# Part12_USB_HUB.net
KiCad netlist of a schematic drawn in Altium Designer
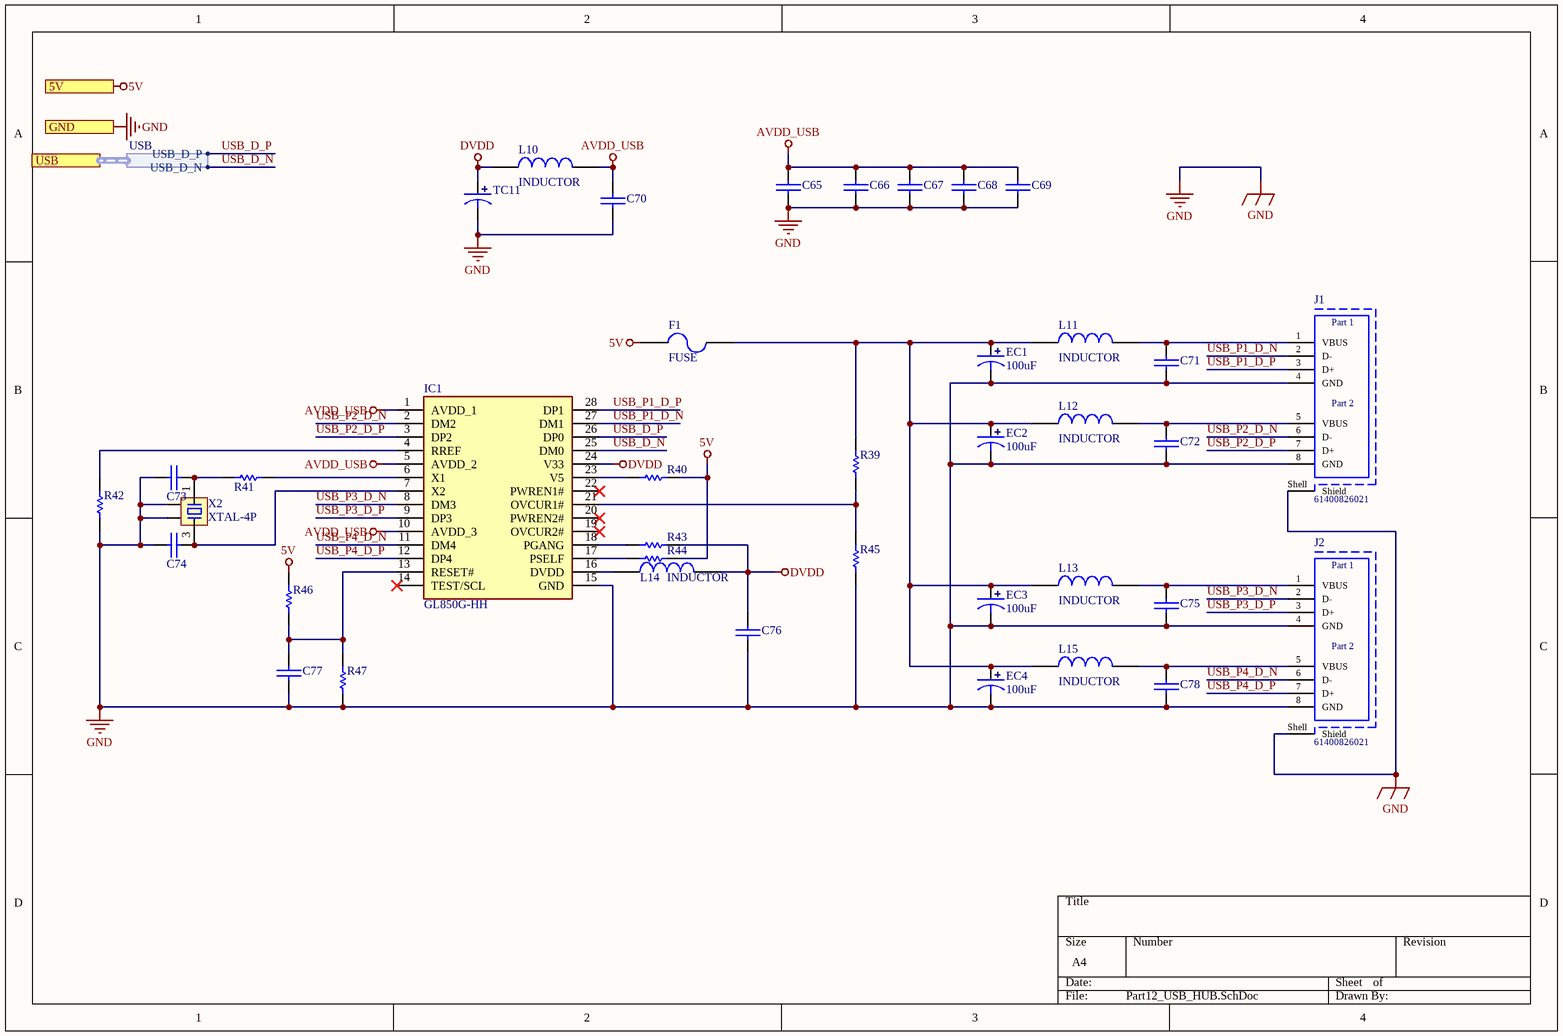
[diagram p0: Part12_USB_HUB.SchDoc]

(export (version "E")
  (design (tool "Eeschema 10.0.6"))
  (components
    (comp (ref "C65")
      (value "100nF/16V")
      (footprint "0402C")
      (description "无极性电容")
      (libsource (lib "电容") (part "CAP"))
    )
    (comp (ref "C66")
      (value "100nF/16V")
      (footprint "0402C")
      (description "无极性电容")
      (libsource (lib "电容") (part "CAP"))
    )
    (comp (ref "C67")
      (value "1uF/16V")
      (footprint "0402C")
      (description "无极性电容")
      (libsource (lib "电容") (part "CAP"))
    )
    (comp (ref "C68")
      (value "1uF/16V")
      (footprint "0402C")
      (description "无极性电容")
      (libsource (lib "电容") (part "CAP"))
    )
    (comp (ref "C69")
      (value "100nF/16V")
      (footprint "0402C")
      (description "无极性电容")
      (libsource (lib "电容") (part "CAP"))
    )
    (comp (ref "C70")
      (value "100nF/16V")
      (footprint "0402C")
      (description "无极性电容")
      (libsource (lib "电容") (part "CAP"))
    )
    (comp (ref "C71")
      (value "100nF/16V")
      (footprint "0603C")
      (description "无极性电容")
      (libsource (lib "电容") (part "CAP"))
    )
    (comp (ref "C72")
      (value "100nF/16V")
      (footprint "0603C")
      (description "无极性电容")
      (libsource (lib "电容") (part "CAP"))
    )
    (comp (ref "C73")
      (value "20pF")
      (footprint "0402C")
      (description "无极性电容")
      (libsource (lib "电容") (part "CAP"))
    )
    (comp (ref "C74")
      (value "20pF")
      (footprint "0402C")
      (description "无极性电容")
      (libsource (lib "电容") (part "CAP"))
    )
    (comp (ref "C75")
      (value "100nF/16V")
      (footprint "0603C")
      (description "无极性电容")
      (libsource (lib "电容") (part "CAP"))
    )
    (comp (ref "C76")
      (value "100nF/16V")
      (footprint "0402C")
      (description "无极性电容")
      (libsource (lib "电容") (part "CAP"))
    )
    (comp (ref "C77")
      (value "1uF/16V")
      (footprint "0402C")
      (description "无极性电容")
      (libsource (lib "电容") (part "CAP"))
    )
    (comp (ref "C78")
      (value "100nF/16V")
      (footprint "0603C")
      (description "无极性电容")
      (libsource (lib "电容") (part "CAP"))
    )
    (comp (ref "EC1")
      (value "100uF")
      (footprint "SMD-EC4.0X4.3X5.4")
      (description "贴片电解电容")
      (libsource (lib "电容") (part "SMD_ECAP"))
    )
    (comp (ref "EC2")
      (value "100uF")
      (footprint "SMD-EC4.0X4.3X5.4")
      (description "贴片电解电容")
      (libsource (lib "电容") (part "SMD_ECAP"))
    )
    (comp (ref "EC3")
      (value "100uF")
      (footprint "SMD-EC4.0X4.3X5.4")
      (description "贴片电解电容")
      (libsource (lib "电容") (part "SMD_ECAP"))
    )
    (comp (ref "EC4")
      (value "100uF")
      (footprint "SMD-EC4.0X4.3X5.4")
      (description "贴片电解电容")
      (libsource (lib "电容") (part "SMD_ECAP"))
    )
    (comp (ref "F1") (value "FUSE") (footprint "FUSE-1210") (libsource (lib "保险丝") (part "FUSE")))
    (comp (ref "IC1")
      (value "GL850G-HH")
      (footprint "SOP65P780X200-28N")
      (description "Integrated Circuit")
      (libsource (lib "SamacSys") (part "GL850G-HH"))
    )
    (comp (ref "J1")
      (value "61400826021")
      (footprint "61400826021")
      (description "USB 2.0 Type A Receptacle WR-COM, Stacked Horizontal, THT")
      (fields (field (name "MANUFACTURER") "Wurth Elektronik") (field (name "PUBLISHER") "WurthElektronik"))
      (libsource (lib "Altium Content Vault") (part "WE-USB-8-1SHLD"))
    )
    (comp (ref "J2")
      (value "61400826021")
      (footprint "61400826021")
      (description "USB 2.0 Type A Receptacle WR-COM, Stacked Horizontal, THT")
      (fields (field (name "MANUFACTURER") "Wurth Elektronik") (field (name "PUBLISHER") "WurthElektronik"))
      (libsource (lib "Altium Content Vault") (part "WE-USB-8-1SHLD"))
    )
    (comp (ref "L10") (value "INDUCTOR") (footprint "0603L") (libsource (lib "电感") (part "INDUCTOR")))
    (comp (ref "L11") (value "INDUCTOR") (footprint "0603L") (libsource (lib "电感") (part "INDUCTOR")))
    (comp (ref "L12") (value "INDUCTOR") (footprint "0603L") (libsource (lib "电感") (part "INDUCTOR")))
    (comp (ref "L13") (value "INDUCTOR") (footprint "0603L") (libsource (lib "电感") (part "INDUCTOR")))
    (comp (ref "L14") (value "INDUCTOR") (footprint "0603L") (libsource (lib "电感") (part "INDUCTOR")))
    (comp (ref "L15") (value "INDUCTOR") (footprint "0603L") (libsource (lib "电感") (part "INDUCTOR")))
    (comp (ref "R39") (value "30K") (footprint "0402R") (libsource (lib "电阻") (part "RES")))
    (comp (ref "R40") (value "0R") (footprint "0402R") (libsource (lib "电阻") (part "RES")))
    (comp (ref "R41") (value "0R") (footprint "0402R") (libsource (lib "电阻") (part "RES")))
    (comp (ref "R42") (value "680R / 1%") (footprint "0402R") (libsource (lib "电阻") (part "RES")))
    (comp (ref "R43") (value "100K") (footprint "0402R") (libsource (lib "电阻") (part "RES")))
    (comp (ref "R44") (value "10K") (footprint "0402R") (libsource (lib "电阻") (part "RES")))
    (comp (ref "R45") (value "30K") (footprint "0402R") (libsource (lib "电阻") (part "RES")))
    (comp (ref "R46") (value "10K") (footprint "0402R") (libsource (lib "电阻") (part "RES")))
    (comp (ref "R47") (value "47K") (footprint "0402R") (libsource (lib "电阻") (part "RES")))
    (comp (ref "TC11")
      (value "4.7uF/6.3V")
      (footprint "TAJ-A/3216")
      (description "钽电容")
      (libsource (lib "电容") (part "TCAP"))
    )
    (comp (ref "X2")
      (value "XTAL-4P")
      (footprint "OSC 3225-4P")
      (description "4脚无源晶振")
      (libsource (lib "晶振") (part "XTAL-4P"))
    )
  )
  (nets
    (net (code "2") (name "/USB_D_N") (class "Default")
      (node (ref "IC1") (pin "25") (pinfunction "DM0_25") (pintype "passive"))
    )
    (net (code "3") (name "/USB_D_P") (class "Default")
      (node (ref "IC1") (pin "26") (pinfunction "DP0_26") (pintype "passive"))
    )
    (net (code "4") (name "/USB_P1_D_N") (class "Default")
      (node (ref "IC1") (pin "27") (pinfunction "DM1_27") (pintype "passive"))
      (node (ref "J1") (pin "2") (pinfunction "D-_2") (pintype "passive"))
    )
    (net (code "5") (name "/USB_P1_D_P") (class "Default")
      (node (ref "IC1") (pin "28") (pinfunction "DP1_28") (pintype "passive"))
      (node (ref "J1") (pin "3") (pinfunction "D+_3") (pintype "passive"))
    )
    (net (code "6") (name "/USB_P2_D_N") (class "Default")
      (node (ref "IC1") (pin "2") (pinfunction "DM2_2") (pintype "passive"))
      (node (ref "J1") (pin "6") (pinfunction "D-_6") (pintype "passive"))
    )
    (net (code "7") (name "/USB_P2_D_P") (class "Default")
      (node (ref "IC1") (pin "3") (pinfunction "DP2_3") (pintype "passive"))
      (node (ref "J1") (pin "7") (pinfunction "D+_7") (pintype "passive"))
    )
    (net (code "8") (name "/USB_P3_D_N") (class "Default")
      (node (ref "IC1") (pin "8") (pinfunction "DM3_8") (pintype "passive"))
      (node (ref "J2") (pin "2") (pinfunction "D-_2") (pintype "passive"))
    )
    (net (code "9") (name "/USB_P3_D_P") (class "Default")
      (node (ref "IC1") (pin "9") (pinfunction "DP3_9") (pintype "passive"))
      (node (ref "J2") (pin "3") (pinfunction "D+_3") (pintype "passive"))
    )
    (net (code "10") (name "/USB_P4_D_N") (class "Default")
      (node (ref "IC1") (pin "11") (pinfunction "DM4_11") (pintype "passive"))
      (node (ref "J2") (pin "6") (pinfunction "D-_6") (pintype "passive"))
    )
    (net (code "11") (name "/USB_P4_D_P") (class "Default")
      (node (ref "IC1") (pin "12") (pinfunction "DP4_12") (pintype "passive"))
      (node (ref "J2") (pin "7") (pinfunction "D+_7") (pintype "passive"))
    )
    (net (code "13") (name "5V") (class "Default")
      (node (ref "F1") (pin "1") (pinfunction "1_1") (pintype "passive"))
      (node (ref "R40") (pin "2") (pinfunction "2_2") (pintype "passive"))
      (node (ref "R44") (pin "2") (pinfunction "2_2") (pintype "passive"))
      (node (ref "R46") (pin "1") (pinfunction "1_1") (pintype "passive"))
    )
    (net (code "14") (name "AVDD_USB") (class "Default")
      (node (ref "C65") (pin "1") (pinfunction "1_1") (pintype "passive"))
      (node (ref "C66") (pin "1") (pinfunction "1_1") (pintype "passive"))
      (node (ref "C67") (pin "1") (pinfunction "1_1") (pintype "passive"))
      (node (ref "C68") (pin "1") (pinfunction "1_1") (pintype "passive"))
      (node (ref "C69") (pin "1") (pinfunction "1_1") (pintype "passive"))
      (node (ref "C70") (pin "1") (pinfunction "1_1") (pintype "passive"))
      (node (ref "IC1") (pin "1") (pinfunction "AVDD_1_1") (pintype "passive"))
      (node (ref "IC1") (pin "10") (pinfunction "AVDD_3_10") (pintype "passive"))
      (node (ref "IC1") (pin "5") (pinfunction "AVDD_2_5") (pintype "passive"))
      (node (ref "L10") (pin "2") (pinfunction "2_2") (pintype "passive"))
    )
    (net (code "15") (name "DVDD") (class "Default")
      (node (ref "C76") (pin "1") (pinfunction "1_1") (pintype "passive"))
      (node (ref "IC1") (pin "24") (pinfunction "V33_24") (pintype "passive"))
      (node (ref "L10") (pin "1") (pinfunction "1_1") (pintype "passive"))
      (node (ref "L14") (pin "2") (pinfunction "2_2") (pintype "passive"))
      (node (ref "R43") (pin "2") (pinfunction "2_2") (pintype "passive"))
      (node (ref "TC11") (pin "1") (pinfunction "1_1") (pintype "passive"))
    )
    (net (code "16") (name "GND") (class "Default")
      (node (ref "C65") (pin "2") (pinfunction "2_2") (pintype "passive"))
      (node (ref "C66") (pin "2") (pinfunction "2_2") (pintype "passive"))
      (node (ref "C67") (pin "2") (pinfunction "2_2") (pintype "passive"))
      (node (ref "C68") (pin "2") (pinfunction "2_2") (pintype "passive"))
      (node (ref "C69") (pin "2") (pinfunction "2_2") (pintype "passive"))
      (node (ref "C70") (pin "2") (pinfunction "2_2") (pintype "passive"))
      (node (ref "C71") (pin "2") (pinfunction "2_2") (pintype "passive"))
      (node (ref "C72") (pin "2") (pinfunction "2_2") (pintype "passive"))
      (node (ref "C73") (pin "1") (pinfunction "1_1") (pintype "passive"))
      (node (ref "C74") (pin "1") (pinfunction "1_1") (pintype "passive"))
      (node (ref "C75") (pin "2") (pinfunction "2_2") (pintype "passive"))
      (node (ref "C76") (pin "2") (pinfunction "2_2") (pintype "passive"))
      (node (ref "C77") (pin "2") (pinfunction "2_2") (pintype "passive"))
      (node (ref "C78") (pin "2") (pinfunction "2_2") (pintype "passive"))
      (node (ref "EC1") (pin "2") (pinfunction "2_2") (pintype "passive"))
      (node (ref "EC2") (pin "2") (pinfunction "2_2") (pintype "passive"))
      (node (ref "EC3") (pin "2") (pinfunction "2_2") (pintype "passive"))
      (node (ref "EC4") (pin "2") (pinfunction "2_2") (pintype "passive"))
      (node (ref "IC1") (pin "15") (pinfunction "GND_15") (pintype "passive"))
      (node (ref "J1") (pin "4") (pinfunction "GND_4") (pintype "passive"))
      (node (ref "J1") (pin "8") (pinfunction "GND_8") (pintype "passive"))
      (node (ref "J1") (pin "Shell") (pinfunction "Shield_Shell") (pintype "passive"))
      (node (ref "J2") (pin "4") (pinfunction "GND_4") (pintype "passive"))
      (node (ref "J2") (pin "8") (pinfunction "GND_8") (pintype "passive"))
      (node (ref "J2") (pin "Shell") (pinfunction "Shield_Shell") (pintype "passive"))
      (node (ref "R42") (pin "2") (pinfunction "2_2") (pintype "passive"))
      (node (ref "R45") (pin "2") (pinfunction "2_2") (pintype "passive"))
      (node (ref "R47") (pin "2") (pinfunction "2_2") (pintype "passive"))
      (node (ref "TC11") (pin "2") (pinfunction "2_2") (pintype "passive"))
      (node (ref "X2") (pin "2") (pinfunction "2_2") (pintype "passive"))
      (node (ref "X2") (pin "4") (pinfunction "4_4") (pintype "passive"))
    )
    (net (code "17") (name "Net-(C71-Pad1)") (class "Default")
      (node (ref "C71") (pin "1") (pinfunction "1_1") (pintype "passive"))
      (node (ref "J1") (pin "1") (pinfunction "VBUS_1") (pintype "passive"))
      (node (ref "L11") (pin "2") (pinfunction "2_2") (pintype "passive"))
    )
    (net (code "18") (name "Net-(C72-Pad1)") (class "Default")
      (node (ref "C72") (pin "1") (pinfunction "1_1") (pintype "passive"))
      (node (ref "J1") (pin "5") (pinfunction "VBUS_5") (pintype "passive"))
      (node (ref "L12") (pin "2") (pinfunction "2_2") (pintype "passive"))
    )
    (net (code "19") (name "Net-(C73-Pad2)") (class "Default")
      (node (ref "C73") (pin "2") (pinfunction "2_2") (pintype "passive"))
      (node (ref "R41") (pin "1") (pinfunction "1_1") (pintype "passive"))
      (node (ref "X2") (pin "1") (pinfunction "1_1") (pintype "passive"))
    )
    (net (code "20") (name "Net-(C75-Pad1)") (class "Default")
      (node (ref "C75") (pin "1") (pinfunction "1_1") (pintype "passive"))
      (node (ref "J2") (pin "1") (pinfunction "VBUS_1") (pintype "passive"))
      (node (ref "L13") (pin "2") (pinfunction "2_2") (pintype "passive"))
    )
    (net (code "21") (name "Net-(C78-Pad1)") (class "Default")
      (node (ref "C78") (pin "1") (pinfunction "1_1") (pintype "passive"))
      (node (ref "J2") (pin "5") (pinfunction "VBUS_5") (pintype "passive"))
      (node (ref "L15") (pin "2") (pinfunction "2_2") (pintype "passive"))
    )
    (net (code "22") (name "Net-(EC1-Pad1)") (class "Default")
      (node (ref "EC1") (pin "1") (pinfunction "1_1") (pintype "passive"))
      (node (ref "EC2") (pin "1") (pinfunction "1_1") (pintype "passive"))
      (node (ref "EC3") (pin "1") (pinfunction "1_1") (pintype "passive"))
      (node (ref "EC4") (pin "1") (pinfunction "1_1") (pintype "passive"))
      (node (ref "F1") (pin "2") (pinfunction "2_2") (pintype "passive"))
      (node (ref "L11") (pin "1") (pinfunction "1_1") (pintype "passive"))
      (node (ref "L12") (pin "1") (pinfunction "1_1") (pintype "passive"))
      (node (ref "L13") (pin "1") (pinfunction "1_1") (pintype "passive"))
      (node (ref "L15") (pin "1") (pinfunction "1_1") (pintype "passive"))
      (node (ref "R39") (pin "1") (pinfunction "1_1") (pintype "passive"))
    )
    (net (code "23") (name "Net-(IC1-DVDD)") (class "Default")
      (node (ref "IC1") (pin "16") (pinfunction "DVDD_16") (pintype "passive"))
      (node (ref "L14") (pin "1") (pinfunction "1_1") (pintype "passive"))
    )
    (net (code "24") (name "Net-(IC1-OVCUR1#)") (class "Default")
      (node (ref "IC1") (pin "21") (pinfunction "OVCUR1#_21") (pintype "passive"))
      (node (ref "R39") (pin "2") (pinfunction "2_2") (pintype "passive"))
      (node (ref "R45") (pin "1") (pinfunction "1_1") (pintype "passive"))
    )
    (net (code "25") (name "Net-(IC1-PGANG)") (class "Default")
      (node (ref "IC1") (pin "18") (pinfunction "PGANG_18") (pintype "passive"))
      (node (ref "R43") (pin "1") (pinfunction "1_1") (pintype "passive"))
    )
    (net (code "26") (name "Net-(IC1-PSELF)") (class "Default")
      (node (ref "IC1") (pin "17") (pinfunction "PSELF_17") (pintype "passive"))
      (node (ref "R44") (pin "1") (pinfunction "1_1") (pintype "passive"))
    )
    (net (code "27") (name "Net-(IC1-RESET#)") (class "Default")
      (node (ref "C77") (pin "1") (pinfunction "1_1") (pintype "passive"))
      (node (ref "IC1") (pin "13") (pinfunction "RESET#_13") (pintype "passive"))
      (node (ref "R46") (pin "2") (pinfunction "2_2") (pintype "passive"))
      (node (ref "R47") (pin "1") (pinfunction "1_1") (pintype "passive"))
    )
    (net (code "28") (name "Net-(IC1-RREF)") (class "Default")
      (node (ref "IC1") (pin "4") (pinfunction "RREF_4") (pintype "passive"))
      (node (ref "R42") (pin "1") (pinfunction "1_1") (pintype "passive"))
    )
    (net (code "29") (name "Net-(IC1-V5)") (class "Default")
      (node (ref "IC1") (pin "23") (pinfunction "V5_23") (pintype "passive"))
      (node (ref "R40") (pin "1") (pinfunction "1_1") (pintype "passive"))
    )
    (net (code "30") (name "Net-(IC1-X1)") (class "Default")
      (node (ref "IC1") (pin "6") (pinfunction "X1_6") (pintype "passive"))
      (node (ref "R41") (pin "2") (pinfunction "2_2") (pintype "passive"))
    )
    (net (code "31") (name "Net-(IC1-X2)") (class "Default")
      (node (ref "C74") (pin "2") (pinfunction "2_2") (pintype "passive"))
      (node (ref "IC1") (pin "7") (pinfunction "X2_7") (pintype "passive"))
      (node (ref "X2") (pin "3") (pinfunction "3_3") (pintype "passive"))
    )
    (net (code "32") (name "unconnected-(IC1-OVCUR2#-Pad19)") (class "Default")
      (node (ref "IC1") (pin "19") (pinfunction "OVCUR2#_19") (pintype "passive+no_connect"))
    )
    (net (code "33") (name "unconnected-(IC1-PWREN1#-Pad22)") (class "Default")
      (node (ref "IC1") (pin "22") (pinfunction "PWREN1#_22") (pintype "passive+no_connect"))
    )
    (net (code "34") (name "unconnected-(IC1-PWREN2#-Pad20)") (class "Default")
      (node (ref "IC1") (pin "20") (pinfunction "PWREN2#_20") (pintype "passive+no_connect"))
    )
    (net (code "35") (name "unconnected-(IC1-TEST{slash}SCL-Pad14)") (class "Default")
      (node (ref "IC1") (pin "14") (pinfunction "TEST/SCL_14") (pintype "passive+no_connect"))
    )
  )
)
